# Space_Pony_Prototype_1.net
KiCad netlist of a schematic drawn in EasyEDA
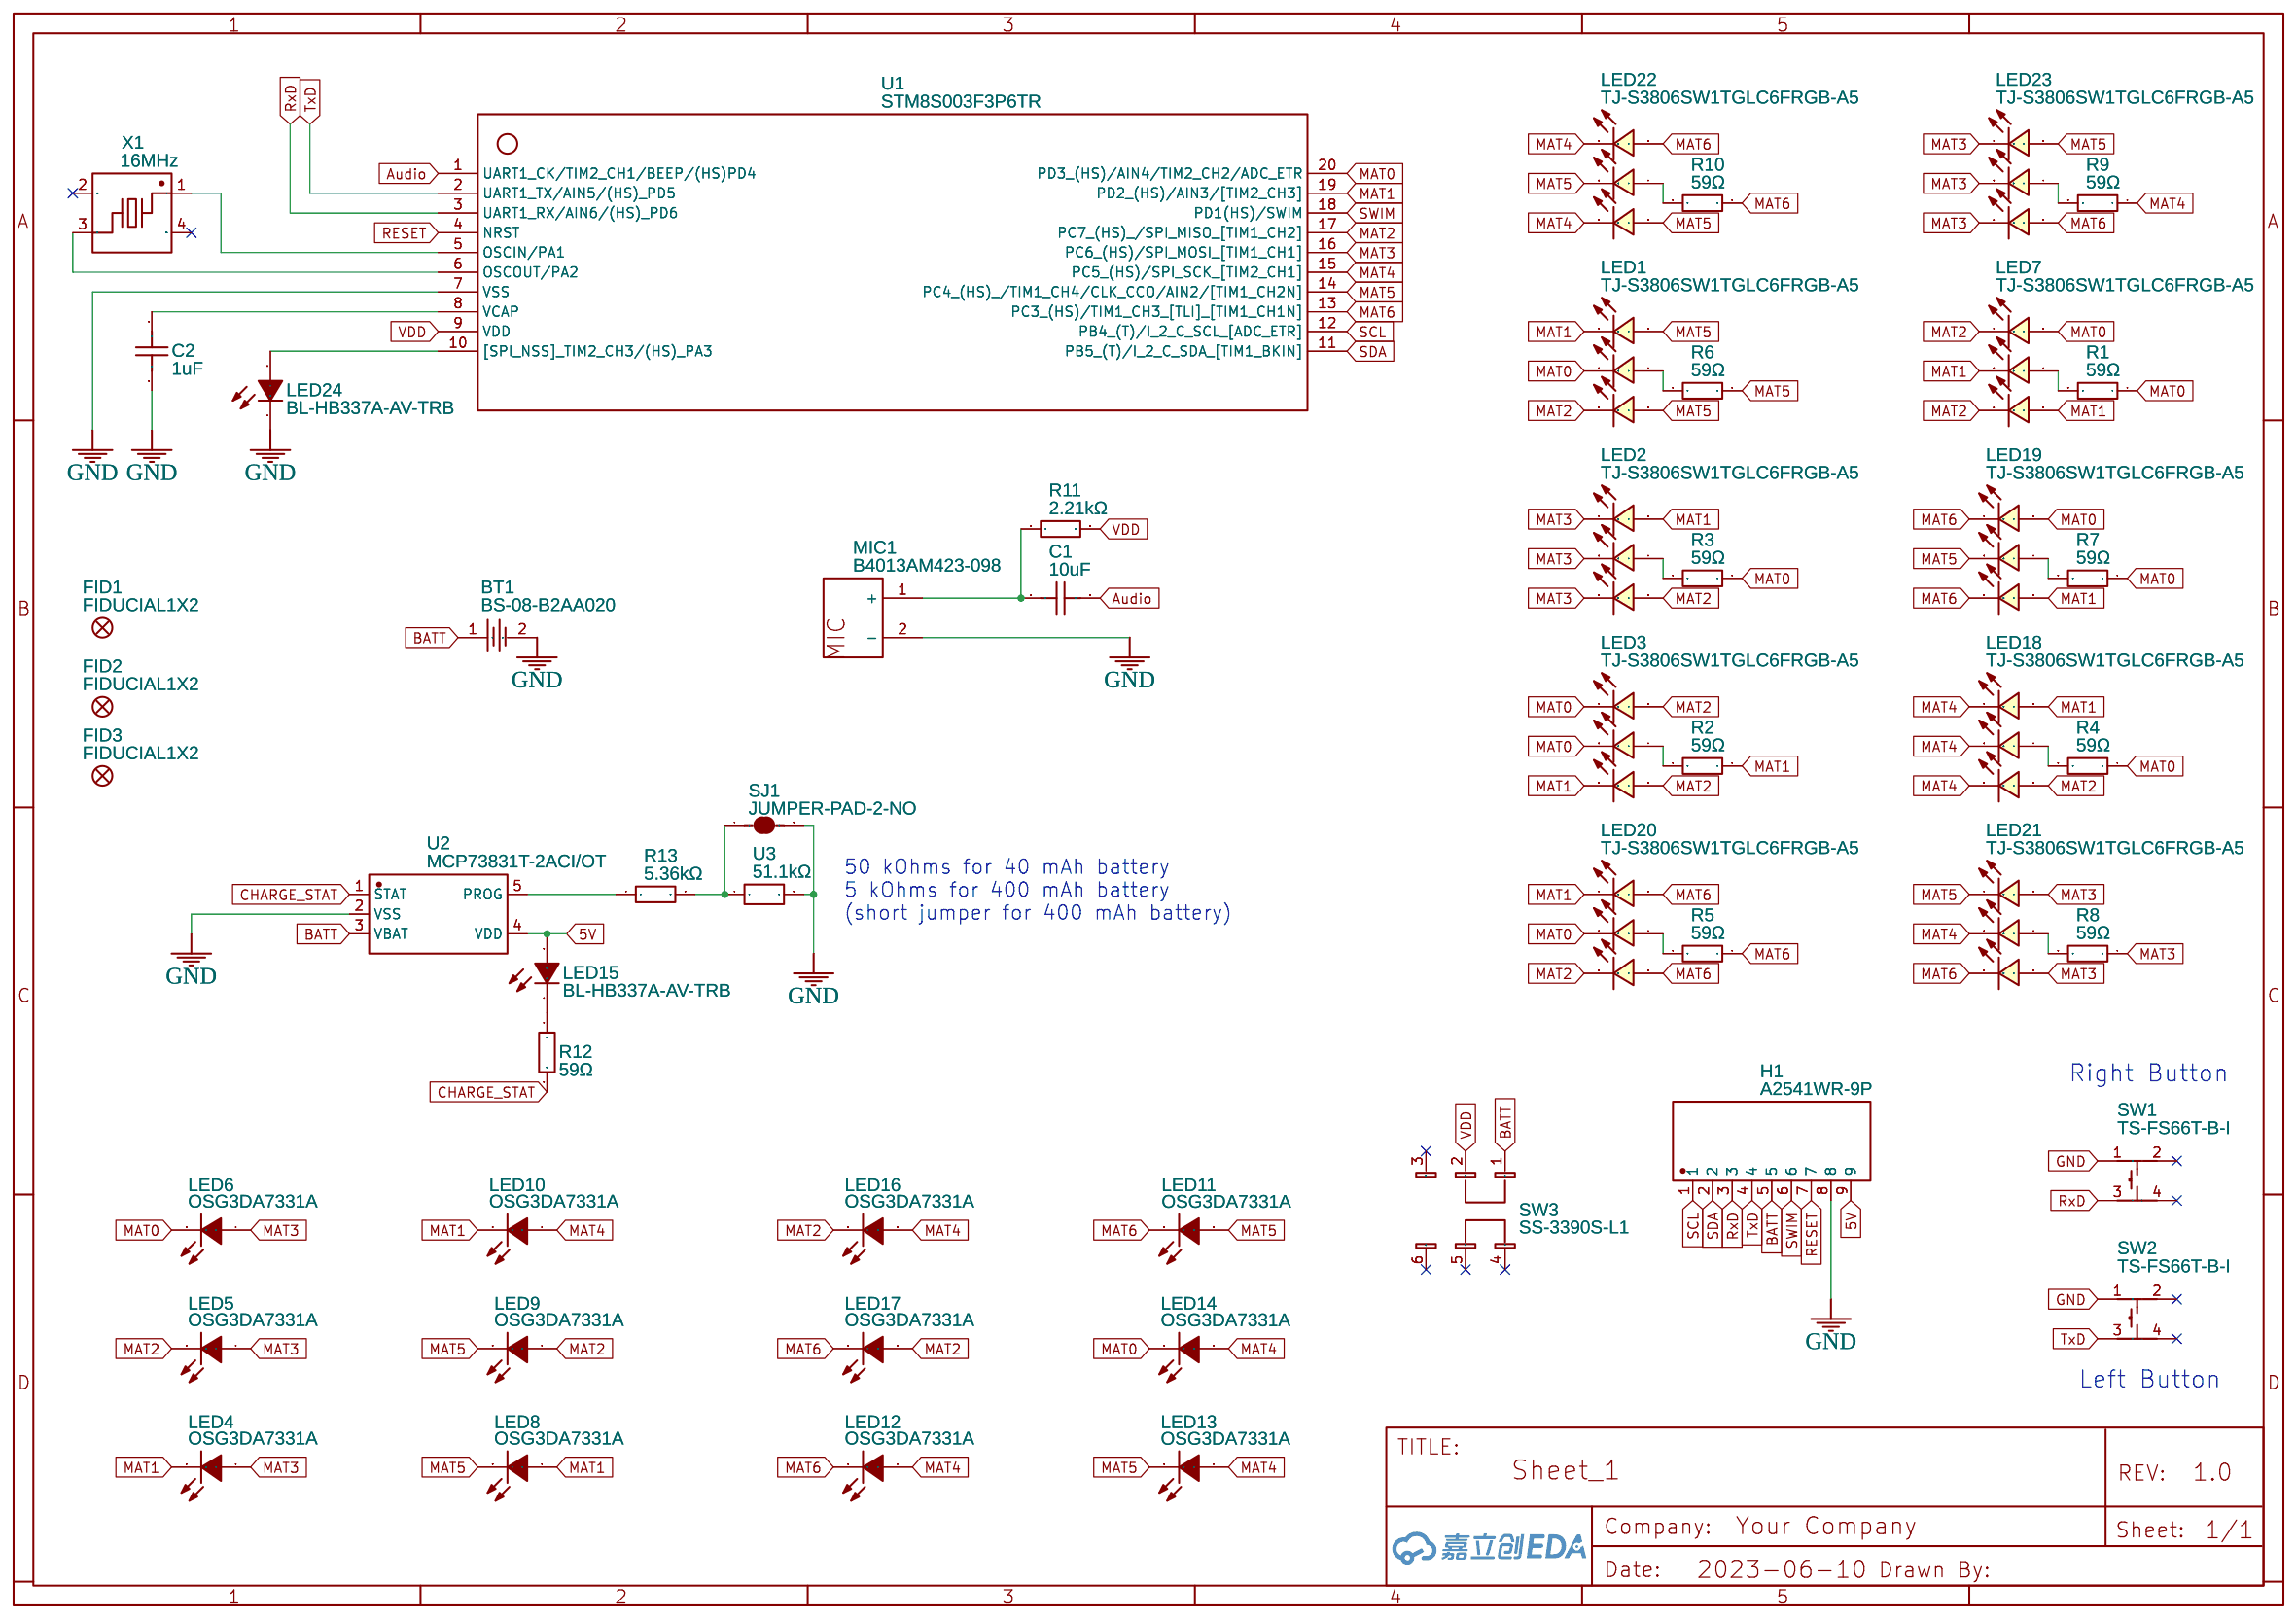
[diagram p0: schematic sheet]

(export (version "E")
  (design (tool "Eeschema 10.0.6"))
  (components
    (comp (ref "BT1")
      (value "BS-08-B2AA020")
      (fields (field (name "BOM_Supplier Part") "C964786"))
      (libsource (lib "") (part "BS-08-B2AA020"))
    )
    (comp (ref "C1")
      (value "10uF")
      (fields
        (field (name "BOM_Manufacturer Part") "GRM155R60J106ME05D")
        (field (name "BOM_Supplier Part") "C723895")
      )
      (libsource (lib "") (part "GRM155R60J106ME05D"))
    )
    (comp (ref "C2")
      (value "1uF")
      (fields
        (field (name "BOM_Manufacturer Part") "CL05B105KQ5NQNC")
        (field (name "BOM_Supplier Part") "C307427")
      )
      (libsource (lib "") (part "CL05B105KQ5NQNC"))
    )
    (comp (ref "FID1") (value "FIDUCIAL1X2") (libsource (lib "") (part "FIDUCIAL1X2")))
    (comp (ref "FID2") (value "FIDUCIAL1X2") (libsource (lib "") (part "FIDUCIAL1X2")))
    (comp (ref "FID3") (value "FIDUCIAL1X2") (libsource (lib "") (part "FIDUCIAL1X2")))
    (comp (ref "H1")
      (value "A2541WR-9P")
      (fields (field (name "BOM_Supplier Part") "C225495"))
      (libsource (lib "") (part "A2541WR-9P"))
    )
    (comp (ref "LED1")
      (value "TJ-S3806SW1TGLC6FRGB-A5")
      (fields (field (name "BOM_Supplier Part") "C601694"))
      (libsource (lib "") (part "TJ-S3806SW1TGLC6FRGB-A5"))
    )
    (comp (ref "LED2")
      (value "TJ-S3806SW1TGLC6FRGB-A5")
      (fields (field (name "BOM_Supplier Part") "C601694"))
      (libsource (lib "") (part "TJ-S3806SW1TGLC6FRGB-A5"))
    )
    (comp (ref "LED3")
      (value "TJ-S3806SW1TGLC6FRGB-A5")
      (fields (field (name "BOM_Supplier Part") "C601694"))
      (libsource (lib "") (part "TJ-S3806SW1TGLC6FRGB-A5"))
    )
    (comp (ref "LED4")
      (value "OSG3DA7331A")
      (fields (field (name "BOM_Supplier Part") "C268274"))
      (libsource (lib "") (part "OSG3DA7331A"))
    )
    (comp (ref "LED5")
      (value "OSG3DA7331A")
      (fields (field (name "BOM_Supplier Part") "C268274"))
      (libsource (lib "") (part "OSG3DA7331A"))
    )
    (comp (ref "LED6")
      (value "OSG3DA7331A")
      (fields (field (name "BOM_Supplier Part") "C268274"))
      (libsource (lib "") (part "OSG3DA7331A"))
    )
    (comp (ref "LED7")
      (value "TJ-S3806SW1TGLC6FRGB-A5")
      (fields (field (name "BOM_Supplier Part") "C601694"))
      (libsource (lib "") (part "TJ-S3806SW1TGLC6FRGB-A5"))
    )
    (comp (ref "LED8")
      (value "OSG3DA7331A")
      (fields (field (name "BOM_Supplier Part") "C268274"))
      (libsource (lib "") (part "OSG3DA7331A"))
    )
    (comp (ref "LED9")
      (value "OSG3DA7331A")
      (fields (field (name "BOM_Supplier Part") "C268274"))
      (libsource (lib "") (part "OSG3DA7331A"))
    )
    (comp (ref "LED10")
      (value "OSG3DA7331A")
      (fields (field (name "BOM_Supplier Part") "C268274"))
      (libsource (lib "") (part "OSG3DA7331A"))
    )
    (comp (ref "LED11")
      (value "OSG3DA7331A")
      (fields (field (name "BOM_Supplier Part") "C268274"))
      (libsource (lib "") (part "OSG3DA7331A"))
    )
    (comp (ref "LED12")
      (value "OSG3DA7331A")
      (fields (field (name "BOM_Supplier Part") "C268274"))
      (libsource (lib "") (part "OSG3DA7331A"))
    )
    (comp (ref "LED13")
      (value "OSG3DA7331A")
      (fields (field (name "BOM_Supplier Part") "C268274"))
      (libsource (lib "") (part "OSG3DA7331A"))
    )
    (comp (ref "LED14")
      (value "OSG3DA7331A")
      (fields (field (name "BOM_Supplier Part") "C268274"))
      (libsource (lib "") (part "OSG3DA7331A"))
    )
    (comp (ref "LED15")
      (value "BL-HB337A-AV-TRB")
      (fields (field (name "BOM_Supplier Part") "C165977"))
      (libsource (lib "") (part "BL-HB337A-AV-TRB"))
    )
    (comp (ref "LED16")
      (value "OSG3DA7331A")
      (fields (field (name "BOM_Supplier Part") "C268274"))
      (libsource (lib "") (part "OSG3DA7331A"))
    )
    (comp (ref "LED17")
      (value "OSG3DA7331A")
      (fields (field (name "BOM_Supplier Part") "C268274"))
      (libsource (lib "") (part "OSG3DA7331A"))
    )
    (comp (ref "LED18")
      (value "TJ-S3806SW1TGLC6FRGB-A5")
      (fields (field (name "BOM_Supplier Part") "C601694"))
      (libsource (lib "") (part "TJ-S3806SW1TGLC6FRGB-A5"))
    )
    (comp (ref "LED19")
      (value "TJ-S3806SW1TGLC6FRGB-A5")
      (fields (field (name "BOM_Supplier Part") "C601694"))
      (libsource (lib "") (part "TJ-S3806SW1TGLC6FRGB-A5"))
    )
    (comp (ref "LED20")
      (value "TJ-S3806SW1TGLC6FRGB-A5")
      (fields (field (name "BOM_Supplier Part") "C601694"))
      (libsource (lib "") (part "TJ-S3806SW1TGLC6FRGB-A5"))
    )
    (comp (ref "LED21")
      (value "TJ-S3806SW1TGLC6FRGB-A5")
      (fields (field (name "BOM_Supplier Part") "C601694"))
      (libsource (lib "") (part "TJ-S3806SW1TGLC6FRGB-A5"))
    )
    (comp (ref "LED22")
      (value "TJ-S3806SW1TGLC6FRGB-A5")
      (fields (field (name "BOM_Supplier Part") "C601694"))
      (libsource (lib "") (part "TJ-S3806SW1TGLC6FRGB-A5"))
    )
    (comp (ref "LED23")
      (value "TJ-S3806SW1TGLC6FRGB-A5")
      (fields (field (name "BOM_Supplier Part") "C601694"))
      (libsource (lib "") (part "TJ-S3806SW1TGLC6FRGB-A5"))
    )
    (comp (ref "LED24")
      (value "BL-HB337A-AV-TRB")
      (fields (field (name "BOM_Supplier Part") "C165977"))
      (libsource (lib "") (part "BL-HB337A-AV-TRB"))
    )
    (comp (ref "MIC1")
      (value "B4013AM423-098")
      (fields (field (name "BOM_Supplier Part") "C2835889"))
      (libsource (lib "") (part "B4013AM423-098"))
    )
    (comp (ref "R1")
      (value "59Ω")
      (fields
        (field (name "BOM_Manufacturer Part") "RTT0259R0FTH")
        (field (name "BOM_Supplier Part") "C159005")
      )
      (libsource (lib "") (part "RTT0259R0FTH"))
    )
    (comp (ref "R2")
      (value "59Ω")
      (fields
        (field (name "BOM_Manufacturer Part") "RTT0259R0FTH")
        (field (name "BOM_Supplier Part") "C159005")
      )
      (libsource (lib "") (part "RTT0259R0FTH"))
    )
    (comp (ref "R3")
      (value "59Ω")
      (fields
        (field (name "BOM_Manufacturer Part") "RTT0259R0FTH")
        (field (name "BOM_Supplier Part") "C159005")
      )
      (libsource (lib "") (part "RTT0259R0FTH"))
    )
    (comp (ref "R4")
      (value "59Ω")
      (fields
        (field (name "BOM_Manufacturer Part") "RTT0259R0FTH")
        (field (name "BOM_Supplier Part") "C159005")
      )
      (libsource (lib "") (part "RTT0259R0FTH"))
    )
    (comp (ref "R5")
      (value "59Ω")
      (fields
        (field (name "BOM_Manufacturer Part") "RTT0259R0FTH")
        (field (name "BOM_Supplier Part") "C159005")
      )
      (libsource (lib "") (part "RTT0259R0FTH"))
    )
    (comp (ref "R6")
      (value "59Ω")
      (fields
        (field (name "BOM_Manufacturer Part") "RTT0259R0FTH")
        (field (name "BOM_Supplier Part") "C159005")
      )
      (libsource (lib "") (part "RTT0259R0FTH"))
    )
    (comp (ref "R7")
      (value "59Ω")
      (fields
        (field (name "BOM_Manufacturer Part") "RTT0259R0FTH")
        (field (name "BOM_Supplier Part") "C159005")
      )
      (libsource (lib "") (part "RTT0259R0FTH"))
    )
    (comp (ref "R8")
      (value "59Ω")
      (fields
        (field (name "BOM_Manufacturer Part") "RTT0259R0FTH")
        (field (name "BOM_Supplier Part") "C159005")
      )
      (libsource (lib "") (part "RTT0259R0FTH"))
    )
    (comp (ref "R9")
      (value "59Ω")
      (fields
        (field (name "BOM_Manufacturer Part") "RTT0259R0FTH")
        (field (name "BOM_Supplier Part") "C159005")
      )
      (libsource (lib "") (part "RTT0259R0FTH"))
    )
    (comp (ref "R10")
      (value "59Ω")
      (fields
        (field (name "BOM_Manufacturer Part") "RTT0259R0FTH")
        (field (name "BOM_Supplier Part") "C159005")
      )
      (libsource (lib "") (part "RTT0259R0FTH"))
    )
    (comp (ref "R11")
      (value "2.21kΩ")
      (fields
        (field (name "BOM_Manufacturer Part") "CR0402FF2211G")
        (field (name "BOM_Supplier Part") "C100313")
      )
      (libsource (lib "") (part "CR0402FF2211G"))
    )
    (comp (ref "R12")
      (value "59Ω")
      (fields
        (field (name "BOM_Manufacturer Part") "RTT0259R0FTH")
        (field (name "BOM_Supplier Part") "C159005")
      )
      (libsource (lib "") (part "RTT0259R0FTH_1"))
    )
    (comp (ref "R13")
      (value "5.36kΩ")
      (fields
        (field (name "BOM_Manufacturer Part") "CR0402FF5361G")
        (field (name "BOM_Supplier Part") "C100471")
      )
      (libsource (lib "") (part "CR0402FF5361G"))
    )
    (comp (ref "SJ1") (value "JUMPER-PAD-2-NO") (libsource (lib "") (part "JUMPER-PAD-2-NO")))
    (comp (ref "SW1")
      (value "TS-FS66T-B-I")
      (fields (field (name "BOM_Supplier Part") "C500114"))
      (libsource (lib "") (part "TS-FS66T-B-I"))
    )
    (comp (ref "SW2")
      (value "TS-FS66T-B-I")
      (fields (field (name "BOM_Supplier Part") "C500114"))
      (libsource (lib "") (part "TS-FS66T-B-I"))
    )
    (comp (ref "SW3")
      (value "SS-3390S-L1")
      (fields (field (name "BOM_Supplier Part") "C318998"))
      (libsource (lib "") (part "SS-3390S-L1"))
    )
    (comp (ref "U1")
      (value "STM8S003F3P6TR")
      (fields (field (name "BOM_Supplier Part") "C52717"))
      (libsource (lib "") (part "STM8S003F3P6TR"))
    )
    (comp (ref "U2")
      (value "MCP73831T-2ACI/OT")
      (fields (field (name "BOM_Supplier Part") "C424093"))
      (libsource (lib "") (part "MCP73831T-2ACI/OT"))
    )
    (comp (ref "U3")
      (value "51.1kΩ")
      (fields
        (field (name "BOM_Manufacturer Part") "MCR01MZPF5112")
        (field (name "BOM_Supplier Part") "C509676")
      )
      (libsource (lib "") (part "MCR01MZPF5112"))
    )
    (comp (ref "X1")
      (value "16MHz")
      (fields
        (field (name "BOM_Manufacturer Part") "XXHBBCNANF-16.000000MHZ")
        (field (name "BOM_Supplier Part") "C521590")
      )
      (libsource (lib "") (part "XXHBBCNANF-16.000000MHZ"))
    )
  )
  (nets
    (net (code "1") (name "5V") (class "Default")
      (node (ref "H1") (pin "9") (pinfunction "9_9") (pintype "unspecified"))
      (node (ref "LED15") (pin "2") (pinfunction "A_2") (pintype "input"))
      (node (ref "U2") (pin "4") (pinfunction "VDD_4") (pintype "unspecified"))
    )
    (net (code "2") (name "Audio") (class "Default")
      (node (ref "C1") (pin "2") (pinfunction "2_2") (pintype "unspecified"))
      (node (ref "U1") (pin "1") (pinfunction "UART1_CK/TIM2_CH1/BEEP/(HS)PD4_1") (pintype "unspecified"))
    )
    (net (code "3") (name "BATT") (class "Default")
      (node (ref "BT1") (pin "1") (pinfunction "1_1") (pintype "input"))
      (node (ref "H1") (pin "5") (pinfunction "5_5") (pintype "unspecified"))
      (node (ref "SW3") (pin "1") (pinfunction "1_1") (pintype "unspecified"))
      (node (ref "U2") (pin "3") (pinfunction "VBAT_3") (pintype "unspecified"))
    )
    (net (code "4") (name "CHARGE_STAT") (class "Default")
      (node (ref "R12") (pin "2") (pinfunction "2_2") (pintype "unspecified"))
      (node (ref "U2") (pin "1") (pinfunction "STAT_1") (pintype "unspecified"))
    )
    (net (code "5") (name "GND") (class "Default")
      (node (ref "BT1") (pin "2") (pinfunction "2_2") (pintype "input"))
      (node (ref "C2") (pin "2") (pinfunction "2_2") (pintype "unspecified"))
      (node (ref "H1") (pin "8") (pinfunction "8_8") (pintype "unspecified"))
      (node (ref "LED24") (pin "1") (pinfunction "K_1") (pintype "input"))
      (node (ref "MIC1") (pin "2") (pinfunction "-_2") (pintype "unspecified"))
      (node (ref "SJ1") (pin "2") (pinfunction "2_2") (pintype "unspecified"))
      (node (ref "SW1") (pin "1") (pinfunction "1_1") (pintype "unspecified"))
      (node (ref "SW2") (pin "1") (pinfunction "1_1") (pintype "unspecified"))
      (node (ref "U1") (pin "7") (pinfunction "VSS_7") (pintype "unspecified"))
      (node (ref "U2") (pin "2") (pinfunction "VSS_2") (pintype "unspecified"))
      (node (ref "U3") (pin "2") (pinfunction "2_2") (pintype "unspecified"))
    )
    (net (code "6") (name "MAT0") (class "Default")
      (node (ref "LED1") (pin "3") (pinfunction "C_3") (pintype "unspecified"))
      (node (ref "LED14") (pin "2") (pinfunction "K_2") (pintype "unspecified"))
      (node (ref "LED19") (pin "2") (pinfunction "A_2") (pintype "unspecified"))
      (node (ref "LED20") (pin "3") (pinfunction "C_3") (pintype "unspecified"))
      (node (ref "LED3") (pin "1") (pinfunction "C_1") (pintype "unspecified"))
      (node (ref "LED3") (pin "3") (pinfunction "C_3") (pintype "unspecified"))
      (node (ref "LED6") (pin "2") (pinfunction "K_2") (pintype "unspecified"))
      (node (ref "LED7") (pin "2") (pinfunction "A_2") (pintype "unspecified"))
      (node (ref "R1") (pin "1") (pinfunction "1_1") (pintype "unspecified"))
      (node (ref "R3") (pin "1") (pinfunction "1_1") (pintype "unspecified"))
      (node (ref "R4") (pin "1") (pinfunction "1_1") (pintype "unspecified"))
      (node (ref "R7") (pin "1") (pinfunction "1_1") (pintype "unspecified"))
      (node (ref "U1") (pin "20") (pinfunction "PD3_(HS)/AIN4/TIM2_CH2/ADC_ETR_20") (pintype "unspecified"))
    )
    (net (code "7") (name "MAT1") (class "Default")
      (node (ref "LED1") (pin "1") (pinfunction "C_1") (pintype "unspecified"))
      (node (ref "LED10") (pin "2") (pinfunction "K_2") (pintype "unspecified"))
      (node (ref "LED18") (pin "2") (pinfunction "A_2") (pintype "unspecified"))
      (node (ref "LED19") (pin "6") (pinfunction "A_6") (pintype "unspecified"))
      (node (ref "LED2") (pin "2") (pinfunction "A_2") (pintype "unspecified"))
      (node (ref "LED20") (pin "1") (pinfunction "C_1") (pintype "unspecified"))
      (node (ref "LED3") (pin "5") (pinfunction "C_5") (pintype "unspecified"))
      (node (ref "LED4") (pin "2") (pinfunction "K_2") (pintype "unspecified"))
      (node (ref "LED7") (pin "3") (pinfunction "C_3") (pintype "unspecified"))
      (node (ref "LED7") (pin "6") (pinfunction "A_6") (pintype "unspecified"))
      (node (ref "LED8") (pin "1") (pinfunction "A_1") (pintype "unspecified"))
      (node (ref "R2") (pin "1") (pinfunction "1_1") (pintype "unspecified"))
      (node (ref "U1") (pin "19") (pinfunction "PD2_(HS)/AIN3/[TIM2_CH3]_19") (pintype "unspecified"))
    )
    (net (code "8") (name "MAT2") (class "Default")
      (node (ref "LED1") (pin "5") (pinfunction "C_5") (pintype "unspecified"))
      (node (ref "LED16") (pin "2") (pinfunction "K_2") (pintype "unspecified"))
      (node (ref "LED17") (pin "1") (pinfunction "A_1") (pintype "unspecified"))
      (node (ref "LED18") (pin "6") (pinfunction "A_6") (pintype "unspecified"))
      (node (ref "LED2") (pin "6") (pinfunction "A_6") (pintype "unspecified"))
      (node (ref "LED20") (pin "5") (pinfunction "C_5") (pintype "unspecified"))
      (node (ref "LED3") (pin "2") (pinfunction "A_2") (pintype "unspecified"))
      (node (ref "LED3") (pin "6") (pinfunction "A_6") (pintype "unspecified"))
      (node (ref "LED5") (pin "2") (pinfunction "K_2") (pintype "unspecified"))
      (node (ref "LED7") (pin "1") (pinfunction "C_1") (pintype "unspecified"))
      (node (ref "LED7") (pin "5") (pinfunction "C_5") (pintype "unspecified"))
      (node (ref "LED9") (pin "1") (pinfunction "A_1") (pintype "unspecified"))
      (node (ref "U1") (pin "17") (pinfunction "PC7_(HS)_/SPI_MISO_[TIM1_CH2]_17") (pintype "unspecified"))
    )
    (net (code "9") (name "MAT3") (class "Default")
      (node (ref "LED2") (pin "1") (pinfunction "C_1") (pintype "unspecified"))
      (node (ref "LED2") (pin "3") (pinfunction "C_3") (pintype "unspecified"))
      (node (ref "LED2") (pin "5") (pinfunction "C_5") (pintype "unspecified"))
      (node (ref "LED21") (pin "2") (pinfunction "A_2") (pintype "unspecified"))
      (node (ref "LED21") (pin "6") (pinfunction "A_6") (pintype "unspecified"))
      (node (ref "LED23") (pin "1") (pinfunction "C_1") (pintype "unspecified"))
      (node (ref "LED23") (pin "3") (pinfunction "C_3") (pintype "unspecified"))
      (node (ref "LED23") (pin "5") (pinfunction "C_5") (pintype "unspecified"))
      (node (ref "LED4") (pin "1") (pinfunction "A_1") (pintype "unspecified"))
      (node (ref "LED5") (pin "1") (pinfunction "A_1") (pintype "unspecified"))
      (node (ref "LED6") (pin "1") (pinfunction "A_1") (pintype "unspecified"))
      (node (ref "R8") (pin "1") (pinfunction "1_1") (pintype "unspecified"))
      (node (ref "U1") (pin "16") (pinfunction "PC6_(HS)/SPI_MOSI_[TIM1_CH1]_16") (pintype "unspecified"))
    )
    (net (code "10") (name "MAT4") (class "Default")
      (node (ref "LED10") (pin "1") (pinfunction "A_1") (pintype "unspecified"))
      (node (ref "LED12") (pin "1") (pinfunction "A_1") (pintype "unspecified"))
      (node (ref "LED13") (pin "1") (pinfunction "A_1") (pintype "unspecified"))
      (node (ref "LED14") (pin "1") (pinfunction "A_1") (pintype "unspecified"))
      (node (ref "LED16") (pin "1") (pinfunction "A_1") (pintype "unspecified"))
      (node (ref "LED18") (pin "1") (pinfunction "C_1") (pintype "unspecified"))
      (node (ref "LED18") (pin "3") (pinfunction "C_3") (pintype "unspecified"))
      (node (ref "LED18") (pin "5") (pinfunction "C_5") (pintype "unspecified"))
      (node (ref "LED21") (pin "3") (pinfunction "C_3") (pintype "unspecified"))
      (node (ref "LED22") (pin "1") (pinfunction "C_1") (pintype "unspecified"))
      (node (ref "LED22") (pin "5") (pinfunction "C_5") (pintype "unspecified"))
      (node (ref "R9") (pin "1") (pinfunction "1_1") (pintype "unspecified"))
      (node (ref "U1") (pin "15") (pinfunction "PC5_(HS)/SPI_SCK_[TIM2_CH1]_15") (pintype "unspecified"))
    )
    (net (code "11") (name "MAT5") (class "Default")
      (node (ref "LED1") (pin "2") (pinfunction "A_2") (pintype "unspecified"))
      (node (ref "LED1") (pin "6") (pinfunction "A_6") (pintype "unspecified"))
      (node (ref "LED11") (pin "1") (pinfunction "A_1") (pintype "unspecified"))
      (node (ref "LED13") (pin "2") (pinfunction "K_2") (pintype "unspecified"))
      (node (ref "LED19") (pin "3") (pinfunction "C_3") (pintype "unspecified"))
      (node (ref "LED21") (pin "1") (pinfunction "C_1") (pintype "unspecified"))
      (node (ref "LED22") (pin "3") (pinfunction "C_3") (pintype "unspecified"))
      (node (ref "LED22") (pin "6") (pinfunction "A_6") (pintype "unspecified"))
      (node (ref "LED23") (pin "2") (pinfunction "A_2") (pintype "unspecified"))
      (node (ref "LED8") (pin "2") (pinfunction "K_2") (pintype "unspecified"))
      (node (ref "LED9") (pin "2") (pinfunction "K_2") (pintype "unspecified"))
      (node (ref "R6") (pin "1") (pinfunction "1_1") (pintype "unspecified"))
      (node (ref "U1") (pin "14") (pinfunction "PC4_(HS)_/TIM1_CH4/CLK_CCO/AIN2/[TIM1_CH2N]_14") (pintype "unspecified"))
    )
    (net (code "12") (name "MAT6") (class "Default")
      (node (ref "LED11") (pin "2") (pinfunction "K_2") (pintype "unspecified"))
      (node (ref "LED12") (pin "2") (pinfunction "K_2") (pintype "unspecified"))
      (node (ref "LED17") (pin "2") (pinfunction "K_2") (pintype "unspecified"))
      (node (ref "LED19") (pin "1") (pinfunction "C_1") (pintype "unspecified"))
      (node (ref "LED19") (pin "5") (pinfunction "C_5") (pintype "unspecified"))
      (node (ref "LED20") (pin "2") (pinfunction "A_2") (pintype "unspecified"))
      (node (ref "LED20") (pin "6") (pinfunction "A_6") (pintype "unspecified"))
      (node (ref "LED21") (pin "5") (pinfunction "C_5") (pintype "unspecified"))
      (node (ref "LED22") (pin "2") (pinfunction "A_2") (pintype "unspecified"))
      (node (ref "LED23") (pin "6") (pinfunction "A_6") (pintype "unspecified"))
      (node (ref "R10") (pin "1") (pinfunction "1_1") (pintype "unspecified"))
      (node (ref "R5") (pin "1") (pinfunction "1_1") (pintype "unspecified"))
      (node (ref "U1") (pin "13") (pinfunction "PC3_(HS)/TIM1_CH3_[TLI]_[TIM1_CH1N]_13") (pintype "unspecified"))
    )
    (net (code "13") (name "Net-(LED1-A-Pad4)") (class "Default")
      (node (ref "LED1") (pin "4") (pinfunction "A_4") (pintype "unspecified"))
      (node (ref "R6") (pin "2") (pinfunction "2_2") (pintype "unspecified"))
    )
    (net (code "14") (name "Net-(LED2-A-Pad4)") (class "Default")
      (node (ref "LED2") (pin "4") (pinfunction "A_4") (pintype "unspecified"))
      (node (ref "R3") (pin "2") (pinfunction "2_2") (pintype "unspecified"))
    )
    (net (code "15") (name "Net-(LED3-A-Pad4)") (class "Default")
      (node (ref "LED3") (pin "4") (pinfunction "A_4") (pintype "unspecified"))
      (node (ref "R2") (pin "2") (pinfunction "2_2") (pintype "unspecified"))
    )
    (net (code "16") (name "Net-(LED7-A-Pad4)") (class "Default")
      (node (ref "LED7") (pin "4") (pinfunction "A_4") (pintype "unspecified"))
      (node (ref "R1") (pin "2") (pinfunction "2_2") (pintype "unspecified"))
    )
    (net (code "17") (name "Net-(LED15-K)") (class "Default")
      (node (ref "LED15") (pin "1") (pinfunction "K_1") (pintype "input"))
      (node (ref "R12") (pin "1") (pinfunction "1_1") (pintype "unspecified"))
    )
    (net (code "18") (name "Net-(LED18-A-Pad4)") (class "Default")
      (node (ref "LED18") (pin "4") (pinfunction "A_4") (pintype "unspecified"))
      (node (ref "R4") (pin "2") (pinfunction "2_2") (pintype "unspecified"))
    )
    (net (code "19") (name "Net-(LED19-A-Pad4)") (class "Default")
      (node (ref "LED19") (pin "4") (pinfunction "A_4") (pintype "unspecified"))
      (node (ref "R7") (pin "2") (pinfunction "2_2") (pintype "unspecified"))
    )
    (net (code "20") (name "Net-(LED20-A-Pad4)") (class "Default")
      (node (ref "LED20") (pin "4") (pinfunction "A_4") (pintype "unspecified"))
      (node (ref "R5") (pin "2") (pinfunction "2_2") (pintype "unspecified"))
    )
    (net (code "21") (name "Net-(LED21-A-Pad4)") (class "Default")
      (node (ref "LED21") (pin "4") (pinfunction "A_4") (pintype "unspecified"))
      (node (ref "R8") (pin "2") (pinfunction "2_2") (pintype "unspecified"))
    )
    (net (code "22") (name "Net-(LED22-A-Pad4)") (class "Default")
      (node (ref "LED22") (pin "4") (pinfunction "A_4") (pintype "unspecified"))
      (node (ref "R10") (pin "2") (pinfunction "2_2") (pintype "unspecified"))
    )
    (net (code "23") (name "Net-(LED23-A-Pad4)") (class "Default")
      (node (ref "LED23") (pin "4") (pinfunction "A_4") (pintype "unspecified"))
      (node (ref "R9") (pin "2") (pinfunction "2_2") (pintype "unspecified"))
    )
    (net (code "24") (name "Net-(LED24-A)") (class "Default")
      (node (ref "LED24") (pin "2") (pinfunction "A_2") (pintype "input"))
      (node (ref "U1") (pin "10") (pinfunction "[SPI_NSS]_TIM2_CH3/(HS)_PA3_10") (pintype "unspecified"))
    )
    (net (code "25") (name "Net-(MIC1-+)") (class "Default")
      (node (ref "C1") (pin "1") (pinfunction "1_1") (pintype "unspecified"))
      (node (ref "MIC1") (pin "1") (pinfunction "+_1") (pintype "unspecified"))
      (node (ref "R11") (pin "1") (pinfunction "1_1") (pintype "input"))
    )
    (net (code "26") (name "Net-(R13-Pad2)") (class "Default")
      (node (ref "R13") (pin "2") (pinfunction "2_2") (pintype "input"))
      (node (ref "SJ1") (pin "1") (pinfunction "1_1") (pintype "unspecified"))
      (node (ref "U3") (pin "1") (pinfunction "1_1") (pintype "unspecified"))
    )
    (net (code "27") (name "Net-(U1-OSCIN{slash}PA1)") (class "Default")
      (node (ref "U1") (pin "5") (pinfunction "OSCIN/PA1_5") (pintype "unspecified"))
      (node (ref "X1") (pin "1") (pinfunction "1_1") (pintype "input"))
    )
    (net (code "28") (name "Net-(U1-OSCOUT{slash}PA2)") (class "Default")
      (node (ref "U1") (pin "6") (pinfunction "OSCOUT/PA2_6") (pintype "unspecified"))
      (node (ref "X1") (pin "3") (pinfunction "3_3") (pintype "input"))
    )
    (net (code "29") (name "Net-(U1-VCAP)") (class "Default")
      (node (ref "C2") (pin "1") (pinfunction "1_1") (pintype "unspecified"))
      (node (ref "U1") (pin "8") (pinfunction "VCAP_8") (pintype "unspecified"))
    )
    (net (code "30") (name "Net-(U2-PROG)") (class "Default")
      (node (ref "R13") (pin "1") (pinfunction "1_1") (pintype "input"))
      (node (ref "U2") (pin "5") (pinfunction "PROG_5") (pintype "unspecified"))
    )
    (net (code "31") (name "RESET") (class "Default")
      (node (ref "H1") (pin "7") (pinfunction "7_7") (pintype "unspecified"))
      (node (ref "U1") (pin "4") (pinfunction "NRST_4") (pintype "unspecified"))
    )
    (net (code "32") (name "RxD") (class "Default")
      (node (ref "H1") (pin "3") (pinfunction "3_3") (pintype "unspecified"))
      (node (ref "SW1") (pin "3") (pinfunction "3_3") (pintype "unspecified"))
      (node (ref "U1") (pin "3") (pinfunction "UART1_RX/AIN6/(HS)_PD6_3") (pintype "unspecified"))
    )
    (net (code "33") (name "SCL") (class "Default")
      (node (ref "H1") (pin "1") (pinfunction "1_1") (pintype "unspecified"))
      (node (ref "U1") (pin "12") (pinfunction "PB4_(T)/I_2_C_SCL_[ADC_ETR]_12") (pintype "unspecified"))
    )
    (net (code "34") (name "SDA") (class "Default")
      (node (ref "H1") (pin "2") (pinfunction "2_2") (pintype "unspecified"))
      (node (ref "U1") (pin "11") (pinfunction "PB5_(T)/I_2_C_SDA_[TIM1_BKIN]_11") (pintype "unspecified"))
    )
    (net (code "35") (name "SWIM") (class "Default")
      (node (ref "H1") (pin "6") (pinfunction "6_6") (pintype "unspecified"))
      (node (ref "U1") (pin "18") (pinfunction "PD1(HS)/SWIM_18") (pintype "unspecified"))
    )
    (net (code "36") (name "TxD") (class "Default")
      (node (ref "H1") (pin "4") (pinfunction "4_4") (pintype "unspecified"))
      (node (ref "SW2") (pin "3") (pinfunction "3_3") (pintype "unspecified"))
      (node (ref "U1") (pin "2") (pinfunction "UART1_TX/AIN5/(HS)_PD5_2") (pintype "unspecified"))
    )
    (net (code "37") (name "VDD") (class "Default")
      (node (ref "R11") (pin "2") (pinfunction "2_2") (pintype "input"))
      (node (ref "SW3") (pin "2") (pinfunction "2_2") (pintype "unspecified"))
      (node (ref "U1") (pin "9") (pinfunction "VDD_9") (pintype "unspecified"))
    )
    (net (code "38") (name "unconnected-(SW1-Pad2)") (class "Default")
      (node (ref "SW1") (pin "2") (pinfunction "2_2") (pintype "unspecified+no_connect"))
    )
    (net (code "39") (name "unconnected-(SW1-Pad4)") (class "Default")
      (node (ref "SW1") (pin "4") (pinfunction "4_4") (pintype "unspecified+no_connect"))
    )
    (net (code "40") (name "unconnected-(SW2-Pad2)") (class "Default")
      (node (ref "SW2") (pin "2") (pinfunction "2_2") (pintype "unspecified+no_connect"))
    )
    (net (code "41") (name "unconnected-(SW2-Pad4)") (class "Default")
      (node (ref "SW2") (pin "4") (pinfunction "4_4") (pintype "unspecified+no_connect"))
    )
    (net (code "42") (name "unconnected-(SW3-Pad3)") (class "Default")
      (node (ref "SW3") (pin "3") (pinfunction "3_3") (pintype "unspecified+no_connect"))
    )
    (net (code "43") (name "unconnected-(SW3-Pad4)") (class "Default")
      (node (ref "SW3") (pin "4") (pinfunction "4_4") (pintype "unspecified+no_connect"))
    )
    (net (code "44") (name "unconnected-(SW3-Pad5)") (class "Default")
      (node (ref "SW3") (pin "5") (pinfunction "5_5") (pintype "unspecified+no_connect"))
    )
    (net (code "45") (name "unconnected-(SW3-Pad6)") (class "Default")
      (node (ref "SW3") (pin "6") (pinfunction "6_6") (pintype "unspecified+no_connect"))
    )
    (net (code "46") (name "unconnected-(X1-GND-Pad2)") (class "Default")
      (node (ref "X1") (pin "2") (pinfunction "GND_2") (pintype "input+no_connect"))
    )
    (net (code "47") (name "unconnected-(X1-GND-Pad4)") (class "Default")
      (node (ref "X1") (pin "4") (pinfunction "GND_4") (pintype "input+no_connect"))
    )
  )
)
